# 2001A.net
KiCad netlist of a schematic drawn in Altium Designer
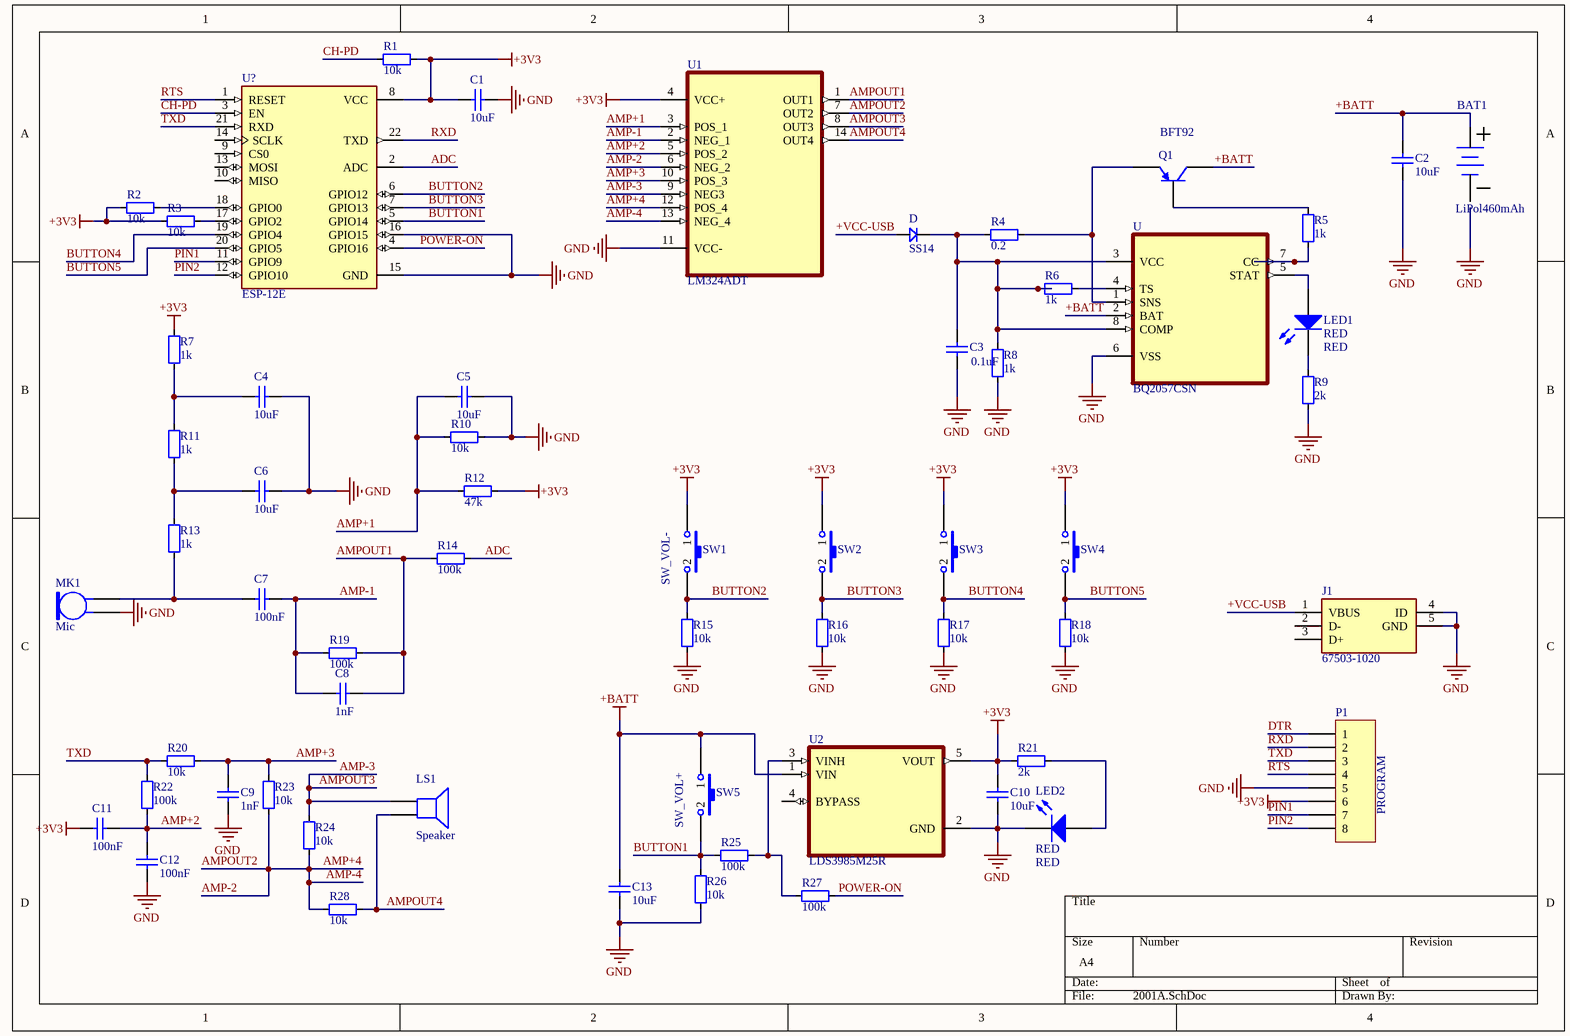
[diagram p0: 2001A.SchDoc]

(export (version "E")
  (design (tool "Eeschema 10.0.6"))
  (components
    (comp (ref "BAT1")
      (value "LiPol460mAh")
      (footprint "LiPol_460mAh")
      (libsource (lib "biblioteka_schematic") (part "Battery"))
    )
    (comp (ref "C1")
      (value "10uF")
      (footprint "0603_CAP")
      (description "Ceramic capacitor")
      (fields (field (name "Comment") "Cap"))
      (libsource (lib "biblioteka_schematic") (part "Cap"))
    )
    (comp (ref "C2")
      (value "10uF")
      (footprint "0603_CAP")
      (description "Ceramic capacitor")
      (fields (field (name "Comment") "Cap"))
      (libsource (lib "biblioteka_schematic") (part "Cap"))
    )
    (comp (ref "C3")
      (value "0.1uF")
      (footprint "0603_CAP")
      (description "Ceramic capacitor")
      (fields (field (name "Comment") "Cap"))
      (libsource (lib "biblioteka_schematic") (part "Cap"))
    )
    (comp (ref "C4")
      (value "10uF")
      (footprint "0603_CAP")
      (description "Ceramic capacitor")
      (fields (field (name "Comment") "Cap"))
      (libsource (lib "biblioteka_schematic") (part "Cap"))
    )
    (comp (ref "C5")
      (value "10uF")
      (footprint "0603_CAP")
      (description "Ceramic capacitor")
      (fields (field (name "Comment") "Cap"))
      (libsource (lib "biblioteka_schematic") (part "Cap"))
    )
    (comp (ref "C6")
      (value "10uF")
      (footprint "0603_CAP")
      (description "Ceramic capacitor")
      (fields (field (name "Comment") "Cap"))
      (libsource (lib "biblioteka_schematic") (part "Cap"))
    )
    (comp (ref "C7")
      (value "100nF")
      (footprint "0603_CAP")
      (description "Ceramic capacitor")
      (fields (field (name "Comment") "Cap"))
      (libsource (lib "biblioteka_schematic") (part "Cap"))
    )
    (comp (ref "C8")
      (value "1nF")
      (footprint "0603_CAP")
      (description "Ceramic capacitor")
      (fields (field (name "Comment") "Cap"))
      (libsource (lib "biblioteka_schematic") (part "Cap"))
    )
    (comp (ref "C9")
      (value "1nF")
      (footprint "0603_CAP")
      (description "Ceramic capacitor")
      (fields (field (name "Comment") "Cap"))
      (libsource (lib "biblioteka_schematic") (part "Cap"))
    )
    (comp (ref "C10")
      (value "10uF")
      (footprint "0603_CAP")
      (description "Ceramic capacitor")
      (fields (field (name "Comment") "Cap"))
      (libsource (lib "biblioteka_schematic") (part "Cap"))
    )
    (comp (ref "C11")
      (value "100nF")
      (footprint "0603_CAP")
      (description "Ceramic capacitor")
      (fields (field (name "Comment") "Cap"))
      (libsource (lib "biblioteka_schematic") (part "Cap"))
    )
    (comp (ref "C12")
      (value "100nF")
      (footprint "0603_CAP")
      (description "Ceramic capacitor")
      (fields (field (name "Comment") "Cap"))
      (libsource (lib "biblioteka_schematic") (part "Cap"))
    )
    (comp (ref "C13")
      (value "10uF")
      (footprint "0603_CAP")
      (description "Ceramic capacitor")
      (fields (field (name "Comment") "Cap"))
      (libsource (lib "biblioteka_schematic") (part "Cap"))
    )
    (comp (ref "D")
      (value "SS14")
      (footprint "SnapEDApcb:DO214")
      (description "Diode Schottky 40V 1A Surface Mount SMA _DO-214AC_")
      (fields (field (name "MF") "ON Semiconductor"))
      (libsource (lib "ss14") (part "SS14"))
    )
    (comp (ref "ESP-12E")
      (value "U?")
      (footprint "XCVR_ESP8266-12E/ESP-12E")
      (fields (field (name "MP") "ESP8266-12E/ESP-12E") (field (name "MF") "AI-Thinker"))
      (libsource (lib "SnapEDAsch") (part "ESP8266-12E/ESP-12E"))
    )
    (comp (ref "J1")
      (value "67503-1020")
      (footprint "SamacSys:67503-1020")
      (description "Connector")
      (fields (field (name "MOUSER PART NUMBER") "538-67503-1020") (field (name "RS PART NUMBER") "1891440"))
      (libsource (lib "usb_otg") (part "67503-1020"))
    )
    (comp (ref "LED1")
      (value "RED")
      (footprint "LED_THT_RED")
      (description "Light-emitting diode")
      (fields (field (name "COLOR") "RED"))
      (libsource (lib "biblioteka_schematic") (part "LED"))
    )
    (comp (ref "LED2")
      (value "RED")
      (footprint "0603")
      (description "Light-emitting diode")
      (fields (field (name "COLOR") "RED"))
      (libsource (lib "biblioteka_schematic") (part "LED"))
    )
    (comp (ref "LS1")
      (value "Speaker")
      (footprint "PIN2")
      (description "Loudspeaker")
      (fields (field (name "PUBLISHER") "Altium Limited"))
      (libsource (lib "Miscellaneous Devices") (part "Speaker"))
    )
    (comp (ref "MK1")
      (value "Mic")
      (footprint "PIN2")
      (description "Microphone")
      (fields (field (name "PUBLISHER") "Altium Limited"))
      (libsource (lib "Miscellaneous Devices") (part "Mic2"))
    )
    (comp (ref "P1")
      (value "PROGRAM")
      (footprint "HDR1X8")
      (description "Header, 8-Pin")
      (fields (field (name "PUBLISHER") "Altium Limited"))
      (libsource (lib "biblioteka_schematic") (part "HDR1X8"))
    )
    (comp (ref "Q1")
      (value "BFT92")
      (footprint "SOT23-3")
      (description "PNP General Purpose Amplifier")
      (fields (field (name "PUBLISHER") "Altium Limited"))
      (libsource (lib "Miscellaneous Devices") (part "2N3906"))
    )
    (comp (ref "R1")
      (value "10k")
      (footprint "0603")
      (description "Resistior")
      (libsource (lib "") (part "RES_2"))
    )
    (comp (ref "R2")
      (value "10k")
      (footprint "0603")
      (description "Resistior")
      (libsource (lib "") (part "RES_2"))
    )
    (comp (ref "R3")
      (value "10k")
      (footprint "0603")
      (description "Resistior")
      (libsource (lib "") (part "RES_2"))
    )
    (comp (ref "R4")
      (value "0.2")
      (footprint "0805")
      (description "Resistior")
      (libsource (lib "") (part "RES_2"))
    )
    (comp (ref "R5")
      (value "1k")
      (footprint "0603")
      (description "Resistior")
      (libsource (lib "") (part "RES_1"))
    )
    (comp (ref "R6")
      (value "1k")
      (footprint "0603")
      (description "Resistior")
      (libsource (lib "") (part "RES_2"))
    )
    (comp (ref "R7")
      (value "1k")
      (footprint "0603")
      (description "Resistior")
      (libsource (lib "") (part "RES_1"))
    )
    (comp (ref "R8")
      (value "1k")
      (footprint "0603")
      (description "Resistior")
      (libsource (lib "") (part "RES_1"))
    )
    (comp (ref "R9")
      (value "2k")
      (footprint "0603")
      (description "Resistior")
      (libsource (lib "") (part "RES_1"))
    )
    (comp (ref "R10")
      (value "10k")
      (footprint "0603")
      (description "Resistior")
      (libsource (lib "") (part "RES_2"))
    )
    (comp (ref "R11")
      (value "1k")
      (footprint "0603")
      (description "Resistior")
      (libsource (lib "") (part "RES_1"))
    )
    (comp (ref "R12")
      (value "47k")
      (footprint "0603")
      (description "Resistior")
      (libsource (lib "") (part "RES_2"))
    )
    (comp (ref "R13")
      (value "1k")
      (footprint "0603")
      (description "Resistior")
      (libsource (lib "") (part "RES_1"))
    )
    (comp (ref "R14")
      (value "100k")
      (footprint "0603")
      (description "Resistior")
      (libsource (lib "") (part "RES_2"))
    )
    (comp (ref "R15")
      (value "10k")
      (footprint "0603")
      (description "Resistior")
      (libsource (lib "") (part "RES_1"))
    )
    (comp (ref "R16")
      (value "10k")
      (footprint "0603")
      (description "Resistior")
      (libsource (lib "") (part "RES_1"))
    )
    (comp (ref "R17")
      (value "10k")
      (footprint "0603")
      (description "Resistior")
      (libsource (lib "") (part "RES_1"))
    )
    (comp (ref "R18")
      (value "10k")
      (footprint "0603")
      (description "Resistior")
      (libsource (lib "") (part "RES_1"))
    )
    (comp (ref "R19")
      (value "100k")
      (footprint "0603")
      (description "Resistior")
      (libsource (lib "") (part "RES_2"))
    )
    (comp (ref "R20")
      (value "10k")
      (footprint "0603")
      (description "Resistior")
      (libsource (lib "") (part "RES_2"))
    )
    (comp (ref "R21")
      (value "2k")
      (footprint "0603")
      (description "Resistior")
      (libsource (lib "") (part "RES_3"))
    )
    (comp (ref "R22")
      (value "100k")
      (footprint "0603")
      (description "Resistior")
      (libsource (lib "biblioteka_schematic") (part "RES"))
    )
    (comp (ref "R23")
      (value "10k")
      (footprint "0603")
      (description "Resistior")
      (libsource (lib "biblioteka_schematic") (part "RES"))
    )
    (comp (ref "R24")
      (value "10k")
      (footprint "0603")
      (description "Resistior")
      (libsource (lib "biblioteka_schematic") (part "RES"))
    )
    (comp (ref "R25")
      (value "100k")
      (footprint "0603")
      (description "Resistior")
      (libsource (lib "") (part "RES_3"))
    )
    (comp (ref "R26")
      (value "10k")
      (footprint "0603")
      (description "Resistior")
      (libsource (lib "biblioteka_schematic") (part "RES"))
    )
    (comp (ref "R27")
      (value "100k")
      (footprint "0603")
      (description "Resistior")
      (libsource (lib "") (part "RES_3"))
    )
    (comp (ref "R28")
      (value "10k")
      (footprint "0603")
      (description "Resistior")
      (libsource (lib "") (part "RES_2"))
    )
    (comp (ref "SW1")
      (value "SW_VOL-")
      (footprint "Micro_Switch")
      (description "Switch")
      (fields (field (name "PUBLISHER") "Altium Limited"))
      (libsource (lib "biblioteka_schematic") (part "Micro_Switch"))
    )
    (comp (ref "SW2")
      (value "SW_VOL-")
      (footprint "Micro_Switch")
      (description "Switch")
      (fields (field (name "PUBLISHER") "Altium Limited"))
      (libsource (lib "biblioteka_schematic") (part "Micro_Switch"))
    )
    (comp (ref "SW3")
      (value "SW_VOL-")
      (footprint "Micro_Switch")
      (description "Switch")
      (fields (field (name "PUBLISHER") "Altium Limited"))
      (libsource (lib "biblioteka_schematic") (part "Micro_Switch"))
    )
    (comp (ref "SW4")
      (value "SW_VOL-")
      (footprint "Micro_Switch")
      (description "Switch")
      (fields (field (name "PUBLISHER") "Altium Limited"))
      (libsource (lib "biblioteka_schematic") (part "Micro_Switch"))
    )
    (comp (ref "SW5")
      (value "SW_VOL+")
      (footprint "Micro_Switch")
      (description "Switch")
      (fields (field (name "PUBLISHER") "Altium Limited"))
      (libsource (lib "biblioteka_schematic") (part "Micro_Switch"))
    )
    (comp (ref "U")
      (value "BQ2057CSN")
      (footprint "SnapEDApcb:SOIC127P600X175-8N")
      (description "Charger IC Lithium Ion/Polymer 8-SOIC")
      (fields (field (name "MF") "Texas Instruments"))
      (libsource (lib "BQ2057CSN") (part "BQ2057CSN"))
    )
    (comp (ref "U1")
      (value "LM324ADT")
      (footprint "SnapEDApcb:SOIC127P600X175-14N")
      (description "LM324A Series 32 V 1.3 MHz Low Power Quad Operational Amplifier - SOIC-14")
      (fields (field (name "MF") "STMicroelectronics"))
      (libsource (lib "lm324adt") (part "LM324ADT"))
    )
    (comp (ref "U2")
      (value "LDS3985M25R")
      (footprint "SOIC127P600X175-14N")
      (description "Linear Voltage Regulator IC 1 Output 300mA SOT-23-5")
      (fields (field (name "MF") "STMicroelectronics"))
      (libsource (lib "lds3985") (part "LDS3985M25R"))
    )
  )
  (nets
    (net (code "1") (name "+3V3") (class "Default")
      (node (ref "C1") (pin "1") (pinfunction "1_1") (pintype "passive"))
      (node (ref "C10") (pin "2") (pinfunction "2_2") (pintype "passive"))
      (node (ref "C11") (pin "1") (pinfunction "1_1") (pintype "passive"))
      (node (ref "ESP-12E") (pin "8") (pinfunction "VCC_8") (pintype "power_in"))
      (node (ref "P1") (pin "6") (pinfunction "6_6") (pintype "passive"))
      (node (ref "R1") (pin "2") (pinfunction "2_2") (pintype "passive"))
      (node (ref "R12") (pin "2") (pinfunction "2_2") (pintype "passive"))
      (node (ref "R2") (pin "1") (pinfunction "1_1") (pintype "passive"))
      (node (ref "R21") (pin "2") (pinfunction "2_2") (pintype "passive"))
      (node (ref "R3") (pin "1") (pinfunction "1_1") (pintype "passive"))
      (node (ref "R7") (pin "1") (pinfunction "1_1") (pintype "passive"))
      (node (ref "SW1") (pin "1") (pinfunction "1_1") (pintype "passive"))
      (node (ref "SW2") (pin "1") (pinfunction "1_1") (pintype "passive"))
      (node (ref "SW3") (pin "1") (pinfunction "1_1") (pintype "passive"))
      (node (ref "SW4") (pin "1") (pinfunction "1_1") (pintype "passive"))
      (node (ref "U1") (pin "4") (pinfunction "VCC+_4") (pintype "power_in"))
      (node (ref "U2") (pin "5") (pinfunction "VOUT_5") (pintype "output"))
    )
    (net (code "2") (name "+BATT") (class "Default")
      (node (ref "C13") (pin "2") (pinfunction "2_2") (pintype "passive"))
      (node (ref "C2") (pin "2") (pinfunction "2_2") (pintype "passive"))
      (node (ref "Q1") (pin "3") (pinfunction "C_3") (pintype "passive"))
      (node (ref "SW5") (pin "1") (pinfunction "1_1") (pintype "passive"))
      (node (ref "U") (pin "2") (pinfunction "BAT_2") (pintype "input"))
      (node (ref "U2") (pin "1") (pinfunction "VIN_1") (pintype "input"))
    )
    (net (code "3") (name "/+VCC-USB") (class "Default")
      (node (ref "D") (pin "ANODE") (pinfunction "ANODE_ANODE") (pintype "bidirectional"))
      (node (ref "J1") (pin "1") (pinfunction "VBUS_1") (pintype "passive"))
    )
    (net (code "4") (name "/ADC") (class "Default")
      (node (ref "ESP-12E") (pin "2") (pinfunction "ADC_2") (pintype "passive"))
      (node (ref "R14") (pin "2") (pinfunction "2_2") (pintype "passive"))
    )
    (net (code "5") (name "/AMP+1") (class "Default")
      (node (ref "C5") (pin "1") (pinfunction "1_1") (pintype "passive"))
      (node (ref "R10") (pin "1") (pinfunction "1_1") (pintype "passive"))
      (node (ref "R12") (pin "1") (pinfunction "1_1") (pintype "passive"))
      (node (ref "U1") (pin "3") (pinfunction "POS_1_3") (pintype "input"))
    )
    (net (code "6") (name "/AMP+2") (class "Default")
      (node (ref "C11") (pin "2") (pinfunction "2_2") (pintype "passive"))
      (node (ref "C12") (pin "2") (pinfunction "2_2") (pintype "passive"))
      (node (ref "R22") (pin "1") (pinfunction "1_1") (pintype "passive"))
      (node (ref "U1") (pin "5") (pinfunction "POS_2_5") (pintype "input"))
    )
    (net (code "7") (name "/AMP+3") (class "Default")
      (node (ref "C9") (pin "2") (pinfunction "2_2") (pintype "passive"))
      (node (ref "R20") (pin "2") (pinfunction "2_2") (pintype "passive"))
      (node (ref "R23") (pin "2") (pinfunction "2_2") (pintype "passive"))
      (node (ref "U1") (pin "10") (pinfunction "POS_3_10") (pintype "input"))
    )
    (net (code "8") (name "/AMP+4") (class "Default")
      (node (ref "R23") (pin "1") (pinfunction "1_1") (pintype "passive"))
      (node (ref "R24") (pin "1") (pinfunction "1_1") (pintype "passive"))
      (node (ref "R28") (pin "1") (pinfunction "1_1") (pintype "passive"))
      (node (ref "U1") (pin "12") (pinfunction "POS_4_12") (pintype "input"))
      (node (ref "U1") (pin "13") (pinfunction "NEG_4_13") (pintype "input"))
      (node (ref "U1") (pin "6") (pinfunction "NEG_2_6") (pintype "input"))
      (node (ref "U1") (pin "7") (pinfunction "OUT2_7") (pintype "output"))
    )
    (net (code "9") (name "/AMP-1") (class "Default")
      (node (ref "C7") (pin "2") (pinfunction "2_2") (pintype "passive"))
      (node (ref "C8") (pin "1") (pinfunction "1_1") (pintype "passive"))
      (node (ref "R19") (pin "1") (pinfunction "1_1") (pintype "passive"))
      (node (ref "U1") (pin "2") (pinfunction "NEG_1_2") (pintype "input"))
    )
    (net (code "10") (name "/AMP-3") (class "Default")
      (node (ref "LS1") (pin "1") (pinfunction "1_1") (pintype "passive"))
      (node (ref "R24") (pin "2") (pinfunction "2_2") (pintype "passive"))
      (node (ref "U1") (pin "8") (pinfunction "OUT3_8") (pintype "output"))
      (node (ref "U1") (pin "9") (pinfunction "NEG3_9") (pintype "input"))
    )
    (net (code "11") (name "/AMPOUT1") (class "Default")
      (node (ref "C8") (pin "2") (pinfunction "2_2") (pintype "passive"))
      (node (ref "R14") (pin "1") (pinfunction "1_1") (pintype "passive"))
      (node (ref "R19") (pin "2") (pinfunction "2_2") (pintype "passive"))
      (node (ref "U1") (pin "1") (pinfunction "OUT1_1") (pintype "output"))
    )
    (net (code "12") (name "/AMPOUT4") (class "Default")
      (node (ref "LS1") (pin "2") (pinfunction "2_2") (pintype "passive"))
      (node (ref "R28") (pin "2") (pinfunction "2_2") (pintype "passive"))
      (node (ref "U1") (pin "14") (pinfunction "OUT4_14") (pintype "output"))
    )
    (net (code "13") (name "/BUTTON1") (class "Default")
      (node (ref "ESP-12E") (pin "5") (pinfunction "GPIO14_5") (pintype "bidirectional"))
      (node (ref "R25") (pin "2") (pinfunction "2_2") (pintype "passive"))
      (node (ref "R26") (pin "2") (pinfunction "2_2") (pintype "passive"))
      (node (ref "SW5") (pin "2") (pinfunction "2_2") (pintype "passive"))
    )
    (net (code "14") (name "/BUTTON2") (class "Default")
      (node (ref "ESP-12E") (pin "6") (pinfunction "GPIO12_6") (pintype "bidirectional"))
      (node (ref "R15") (pin "1") (pinfunction "1_1") (pintype "passive"))
      (node (ref "SW1") (pin "2") (pinfunction "2_2") (pintype "passive"))
    )
    (net (code "15") (name "/BUTTON3") (class "Default")
      (node (ref "ESP-12E") (pin "7") (pinfunction "GPIO13_7") (pintype "bidirectional"))
      (node (ref "R16") (pin "1") (pinfunction "1_1") (pintype "passive"))
      (node (ref "SW2") (pin "2") (pinfunction "2_2") (pintype "passive"))
    )
    (net (code "16") (name "/BUTTON4") (class "Default")
      (node (ref "ESP-12E") (pin "19") (pinfunction "GPIO4_19") (pintype "bidirectional"))
      (node (ref "R17") (pin "1") (pinfunction "1_1") (pintype "passive"))
      (node (ref "SW3") (pin "2") (pinfunction "2_2") (pintype "passive"))
    )
    (net (code "17") (name "/BUTTON5") (class "Default")
      (node (ref "ESP-12E") (pin "20") (pinfunction "GPIO5_20") (pintype "bidirectional"))
      (node (ref "R18") (pin "1") (pinfunction "1_1") (pintype "passive"))
      (node (ref "SW4") (pin "2") (pinfunction "2_2") (pintype "passive"))
    )
    (net (code "18") (name "/CH-PD") (class "Default")
      (node (ref "ESP-12E") (pin "3") (pinfunction "EN_3") (pintype "input"))
      (node (ref "R1") (pin "1") (pinfunction "1_1") (pintype "passive"))
    )
    (net (code "19") (name "/DTR") (class "Default")
      (node (ref "P1") (pin "1") (pinfunction "1_1") (pintype "passive"))
    )
    (net (code "20") (name "/PIN1") (class "Default")
      (node (ref "ESP-12E") (pin "11") (pinfunction "GPIO9_11") (pintype "bidirectional"))
      (node (ref "P1") (pin "7") (pinfunction "7_7") (pintype "passive"))
    )
    (net (code "21") (name "/PIN2") (class "Default")
      (node (ref "ESP-12E") (pin "12") (pinfunction "GPIO10_12") (pintype "bidirectional"))
      (node (ref "P1") (pin "8") (pinfunction "8_8") (pintype "passive"))
    )
    (net (code "22") (name "/POWER-ON") (class "Default")
      (node (ref "ESP-12E") (pin "4") (pinfunction "GPIO16_4") (pintype "bidirectional"))
      (node (ref "R27") (pin "1") (pinfunction "1_1") (pintype "passive"))
    )
    (net (code "23") (name "/RTS") (class "Default")
      (node (ref "ESP-12E") (pin "1") (pinfunction "RESET_1") (pintype "input"))
      (node (ref "P1") (pin "4") (pinfunction "4_4") (pintype "passive"))
    )
    (net (code "24") (name "/RXD") (class "Default")
      (node (ref "ESP-12E") (pin "22") (pinfunction "TXD_22") (pintype "output"))
      (node (ref "P1") (pin "2") (pinfunction "2_2") (pintype "passive"))
    )
    (net (code "25") (name "/TXD") (class "Default")
      (node (ref "ESP-12E") (pin "21") (pinfunction "RXD_21") (pintype "input"))
      (node (ref "P1") (pin "3") (pinfunction "3_3") (pintype "passive"))
      (node (ref "R20") (pin "1") (pinfunction "1_1") (pintype "passive"))
      (node (ref "R22") (pin "2") (pinfunction "2_2") (pintype "passive"))
    )
    (net (code "26") (name "GND") (class "Default")
      (node (ref "C1") (pin "2") (pinfunction "2_2") (pintype "passive"))
      (node (ref "C10") (pin "1") (pinfunction "1_1") (pintype "passive"))
      (node (ref "C12") (pin "1") (pinfunction "1_1") (pintype "passive"))
      (node (ref "C13") (pin "1") (pinfunction "1_1") (pintype "passive"))
      (node (ref "C2") (pin "1") (pinfunction "1_1") (pintype "passive"))
      (node (ref "C3") (pin "1") (pinfunction "1_1") (pintype "passive"))
      (node (ref "C4") (pin "2") (pinfunction "2_2") (pintype "passive"))
      (node (ref "C5") (pin "2") (pinfunction "2_2") (pintype "passive"))
      (node (ref "C6") (pin "2") (pinfunction "2_2") (pintype "passive"))
      (node (ref "C9") (pin "1") (pinfunction "1_1") (pintype "passive"))
      (node (ref "ESP-12E") (pin "15") (pinfunction "GND_15") (pintype "power_in"))
      (node (ref "ESP-12E") (pin "16") (pinfunction "GPIO15_16") (pintype "bidirectional"))
      (node (ref "J1") (pin "4") (pinfunction "ID_4") (pintype "passive"))
      (node (ref "J1") (pin "5") (pinfunction "GND_5") (pintype "passive"))
      (node (ref "LED2") (pin "2") (pinfunction "K_2") (pintype "passive"))
      (node (ref "MK1") (pin "1") (pinfunction "1_1") (pintype "passive"))
      (node (ref "P1") (pin "5") (pinfunction "5_5") (pintype "passive"))
      (node (ref "R10") (pin "2") (pinfunction "2_2") (pintype "passive"))
      (node (ref "R15") (pin "2") (pinfunction "2_2") (pintype "passive"))
      (node (ref "R16") (pin "2") (pinfunction "2_2") (pintype "passive"))
      (node (ref "R17") (pin "2") (pinfunction "2_2") (pintype "passive"))
      (node (ref "R18") (pin "2") (pinfunction "2_2") (pintype "passive"))
      (node (ref "R26") (pin "1") (pinfunction "1_1") (pintype "passive"))
      (node (ref "R8") (pin "2") (pinfunction "2_2") (pintype "passive"))
      (node (ref "R9") (pin "2") (pinfunction "2_2") (pintype "passive"))
      (node (ref "U") (pin "6") (pinfunction "VSS_6") (pintype "power_in"))
      (node (ref "U1") (pin "11") (pinfunction "VCC-_11") (pintype "power_in"))
      (node (ref "U2") (pin "2") (pinfunction "GND_2") (pintype "power_in"))
    )
    (net (code "27") (name "Net-(C4-Pad1)") (class "Default")
      (node (ref "C4") (pin "1") (pinfunction "1_1") (pintype "passive"))
      (node (ref "R11") (pin "1") (pinfunction "1_1") (pintype "passive"))
      (node (ref "R7") (pin "2") (pinfunction "2_2") (pintype "passive"))
    )
    (net (code "28") (name "Net-(C6-Pad1)") (class "Default")
      (node (ref "C6") (pin "1") (pinfunction "1_1") (pintype "passive"))
      (node (ref "R11") (pin "2") (pinfunction "2_2") (pintype "passive"))
      (node (ref "R13") (pin "1") (pinfunction "1_1") (pintype "passive"))
    )
    (net (code "29") (name "Net-(C7-Pad1)") (class "Default")
      (node (ref "C7") (pin "1") (pinfunction "1_1") (pintype "passive"))
      (node (ref "MK1") (pin "2") (pinfunction "2_2") (pintype "passive"))
      (node (ref "R13") (pin "2") (pinfunction "2_2") (pintype "passive"))
    )
    (net (code "30") (name "Net-(D-KATHODE)") (class "Default")
      (node (ref "C3") (pin "2") (pinfunction "2_2") (pintype "passive"))
      (node (ref "D") (pin "CATHODE") (pinfunction "KATHODE_CATHODE") (pintype "bidirectional"))
      (node (ref "R4") (pin "1") (pinfunction "1_1") (pintype "passive"))
      (node (ref "R6") (pin "1") (pinfunction "1_1") (pintype "passive"))
      (node (ref "R8") (pin "1") (pinfunction "1_1") (pintype "passive"))
      (node (ref "U") (pin "3") (pinfunction "VCC_3") (pintype "power_in"))
      (node (ref "U") (pin "8") (pinfunction "COMP_8") (pintype "input"))
    )
    (net (code "31") (name "Net-(ESP-12E-GPIO0)") (class "Default")
      (node (ref "ESP-12E") (pin "18") (pinfunction "GPIO0_18") (pintype "bidirectional"))
      (node (ref "R2") (pin "2") (pinfunction "2_2") (pintype "passive"))
    )
    (net (code "32") (name "Net-(ESP-12E-GPIO2)") (class "Default")
      (node (ref "ESP-12E") (pin "17") (pinfunction "GPIO2_17") (pintype "bidirectional"))
      (node (ref "R3") (pin "2") (pinfunction "2_2") (pintype "passive"))
    )
    (net (code "33") (name "Net-(LED1-A)") (class "Default")
      (node (ref "LED1") (pin "1") (pinfunction "A_1") (pintype "passive"))
      (node (ref "U") (pin "5") (pinfunction "STAT_5") (pintype "output"))
    )
    (net (code "34") (name "Net-(LED1-K)") (class "Default")
      (node (ref "LED1") (pin "2") (pinfunction "K_2") (pintype "passive"))
      (node (ref "R9") (pin "1") (pinfunction "1_1") (pintype "passive"))
    )
    (net (code "35") (name "Net-(LED2-A)") (class "Default")
      (node (ref "LED2") (pin "1") (pinfunction "A_1") (pintype "passive"))
      (node (ref "R21") (pin "1") (pinfunction "1_1") (pintype "passive"))
    )
    (net (code "36") (name "Net-(Q1-B)") (class "Default")
      (node (ref "Q1") (pin "2") (pinfunction "B_2") (pintype "passive"))
      (node (ref "R5") (pin "1") (pinfunction "1_1") (pintype "passive"))
    )
    (net (code "37") (name "Net-(Q1-E)") (class "Default")
      (node (ref "Q1") (pin "1") (pinfunction "E_1") (pintype "passive"))
      (node (ref "R4") (pin "2") (pinfunction "2_2") (pintype "passive"))
      (node (ref "U") (pin "1") (pinfunction "SNS_1") (pintype "input"))
    )
    (net (code "38") (name "Net-(U-CC)") (class "Default")
      (node (ref "R5") (pin "2") (pinfunction "2_2") (pintype "passive"))
      (node (ref "U") (pin "7") (pinfunction "CC_7") (pintype "output"))
    )
    (net (code "39") (name "Net-(U-TS)") (class "Default")
      (node (ref "R6") (pin "2") (pinfunction "2_2") (pintype "passive"))
      (node (ref "U") (pin "4") (pinfunction "TS_4") (pintype "input"))
    )
    (net (code "40") (name "Net-(U2-VINH)") (class "Default")
      (node (ref "R25") (pin "1") (pinfunction "1_1") (pintype "passive"))
      (node (ref "R27") (pin "2") (pinfunction "2_2") (pintype "passive"))
      (node (ref "U2") (pin "3") (pinfunction "VINH_3") (pintype "input"))
    )
    (net (code "41") (name "unconnected-(ESP-12E-CS0-Pad9)") (class "Default")
      (node (ref "ESP-12E") (pin "9") (pinfunction "CS0_9") (pintype "input"))
    )
    (net (code "42") (name "unconnected-(ESP-12E-MISO-Pad10)") (class "Default")
      (node (ref "ESP-12E") (pin "10") (pinfunction "MISO_10") (pintype "bidirectional"))
    )
    (net (code "43") (name "unconnected-(ESP-12E-MOSI-Pad13)") (class "Default")
      (node (ref "ESP-12E") (pin "13") (pinfunction "MOSI_13") (pintype "bidirectional"))
    )
    (net (code "44") (name "unconnected-(ESP-12E-SCLK-Pad14)") (class "Default")
      (node (ref "ESP-12E") (pin "14") (pinfunction "SCLK_14") (pintype "input"))
    )
    (net (code "45") (name "unconnected-(J1-D+-Pad3)") (class "Default")
      (node (ref "J1") (pin "3") (pinfunction "D+_3") (pintype "passive"))
    )
    (net (code "46") (name "unconnected-(J1-D--Pad2)") (class "Default")
      (node (ref "J1") (pin "2") (pinfunction "D-_2") (pintype "passive"))
    )
    (net (code "47") (name "unconnected-(U2-BYPASS-Pad4)") (class "Default")
      (node (ref "U2") (pin "4") (pinfunction "BYPASS_4") (pintype "bidirectional"))
    )
  )
)
